# KinectIP.net
KiCad netlist of a schematic drawn in EAGLE
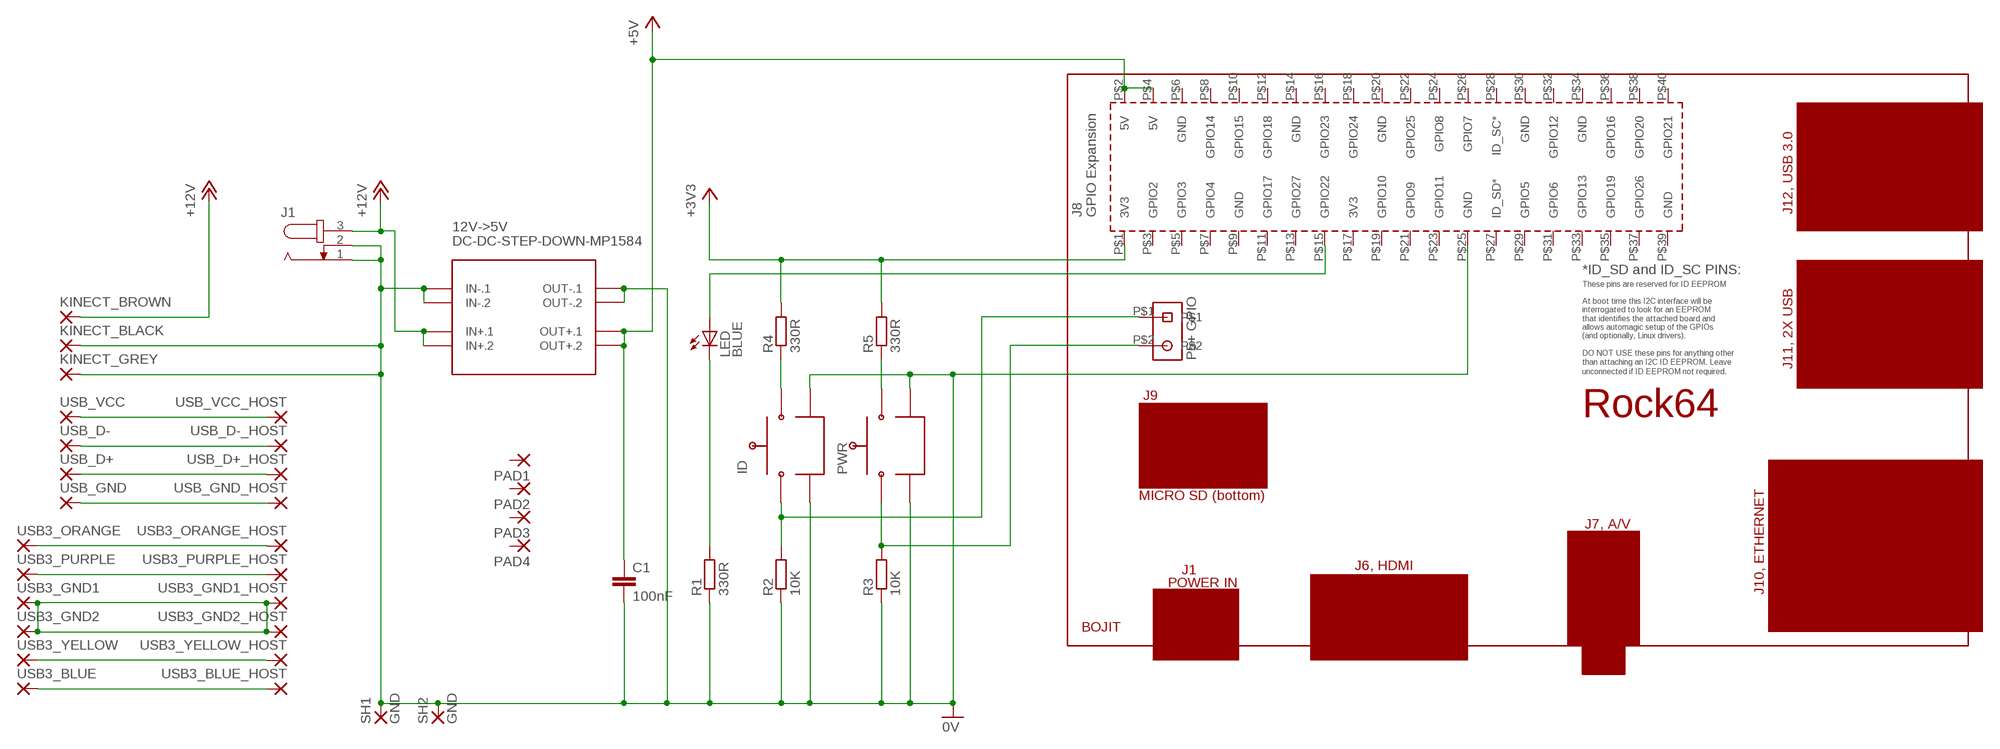
[diagram p0: schematic, sheet 1]

(export (version "E")
  (design (tool "Eeschema 10.0.6"))
  (components
    (comp (ref "12V->5V")
      (value "DC-DC-STEP-DOWN-MP1584")
      (footprint "eagle-import:DC-DC-STEP-DOWN-MP1584")
      (libsource (lib "eagle-import") (part "DC-DC-STEP-DOWN-MP1584"))
    )
    (comp (ref "C1")
      (value "100nF")
      (footprint "eagle-import:C0805K")
      (libsource (lib "eagle-import") (part "C-EUC0805K"))
    )
    (comp (ref "ID")
      (value "RIGHT-ANGLE-SWITCH")
      (footprint "eagle-import:RIGHT-ANGLE-SWITCH")
      (libsource (lib "eagle-import") (part "RIGHT-ANGLE-SWITCH"))
    )
    (comp (ref "J1")
      (value "JACK-PLUG-SLOTTED0")
      (footprint "eagle-import:SPC4077")
      (libsource (lib "eagle-import") (part "JACK-PLUG-SLOTTED0"))
    )
    (comp (ref "KINECT_BLACK")
      (value "SMD2")
      (footprint "eagle-import:SMD1,27-2,54")
      (libsource (lib "eagle-import") (part "SMD2"))
    )
    (comp (ref "KINECT_BROWN")
      (value "SMD2")
      (footprint "eagle-import:SMD1,27-2,54")
      (libsource (lib "eagle-import") (part "SMD2"))
    )
    (comp (ref "KINECT_GREY")
      (value "SMD2")
      (footprint "eagle-import:SMD1,27-2,54")
      (libsource (lib "eagle-import") (part "SMD2"))
    )
    (comp (ref "LED")
      (value "BLUE")
      (footprint "eagle-import:LED-90-DEG")
      (libsource (lib "eagle-import") (part "LED-90-DEG"))
    )
    (comp (ref "P5+")
      (value "2PIN-FEMALE-HEADER")
      (footprint "eagle-import:2PIN-FEMALE-HEADER")
      (libsource (lib "eagle-import") (part "2PIN-FEMALE-HEADER"))
    )
    (comp (ref "PAD1")
      (value "1,6/0,8")
      (footprint "eagle-import:1,6_0,8")
      (libsource (lib "eagle-import") (part "1,6/0,8"))
    )
    (comp (ref "PAD2")
      (value "1,6/0,8")
      (footprint "eagle-import:1,6_0,8")
      (libsource (lib "eagle-import") (part "1,6/0,8"))
    )
    (comp (ref "PAD3")
      (value "1,6/0,8")
      (footprint "eagle-import:1,6_0,8")
      (libsource (lib "eagle-import") (part "1,6/0,8"))
    )
    (comp (ref "PAD4")
      (value "1,6/0,8")
      (footprint "eagle-import:1,6_0,8")
      (libsource (lib "eagle-import") (part "1,6/0,8"))
    )
    (comp (ref "PCB2")
      (value "ROCK64ROCK64")
      (footprint "eagle-import:ROCK64")
      (libsource (lib "eagle-import") (part "ROCK64ROCK64"))
    )
    (comp (ref "PWR")
      (value "RIGHT-ANGLE-SWITCH")
      (footprint "eagle-import:RIGHT-ANGLE-SWITCH")
      (libsource (lib "eagle-import") (part "RIGHT-ANGLE-SWITCH"))
    )
    (comp (ref "R1")
      (value "330R")
      (footprint "eagle-import:R0805")
      (libsource (lib "eagle-import") (part "R-EU_R0805"))
    )
    (comp (ref "R2")
      (value "10K")
      (footprint "eagle-import:R0805")
      (libsource (lib "eagle-import") (part "R-EU_R0805"))
    )
    (comp (ref "R3")
      (value "10K")
      (footprint "eagle-import:R0805")
      (libsource (lib "eagle-import") (part "R-EU_R0805"))
    )
    (comp (ref "R4")
      (value "330R")
      (footprint "eagle-import:R0805")
      (libsource (lib "eagle-import") (part "R-EU_R0805"))
    )
    (comp (ref "R5")
      (value "330R")
      (footprint "eagle-import:R0805")
      (libsource (lib "eagle-import") (part "R-EU_R0805"))
    )
    (comp (ref "SH1")
      (value "GND")
      (footprint "eagle-import:SMD2,54-5,08")
      (libsource (lib "eagle-import") (part "SMD5"))
    )
    (comp (ref "SH2")
      (value "GND")
      (footprint "eagle-import:SMD2,54-5,08")
      (libsource (lib "eagle-import") (part "SMD5"))
    )
    (comp (ref "U$1")
      (value "BOJIT_COPPER")
      (footprint "eagle-import:BOJIT_LARGE_COPPER")
      (libsource (lib "eagle-import") (part "BOJIT_COPPER"))
    )
    (comp (ref "USB3_BLUE")
      (value "SMD2")
      (footprint "eagle-import:SMD1,27-2,54")
      (libsource (lib "eagle-import") (part "SMD2"))
    )
    (comp (ref "USB3_BLUE_HOST")
      (value "SMD2")
      (footprint "eagle-import:SMD1,27-2,54")
      (libsource (lib "eagle-import") (part "SMD2"))
    )
    (comp (ref "USB3_GND1")
      (value "SMD2")
      (footprint "eagle-import:SMD1,27-2,54")
      (libsource (lib "eagle-import") (part "SMD2"))
    )
    (comp (ref "USB3_GND1_HOST")
      (value "SMD2")
      (footprint "eagle-import:SMD1,27-2,54")
      (libsource (lib "eagle-import") (part "SMD2"))
    )
    (comp (ref "USB3_GND2")
      (value "SMD2")
      (footprint "eagle-import:SMD1,27-2,54")
      (libsource (lib "eagle-import") (part "SMD2"))
    )
    (comp (ref "USB3_GND2_HOST")
      (value "SMD2")
      (footprint "eagle-import:SMD1,27-2,54")
      (libsource (lib "eagle-import") (part "SMD2"))
    )
    (comp (ref "USB3_ORANGE")
      (value "SMD2")
      (footprint "eagle-import:SMD1,27-2,54")
      (libsource (lib "eagle-import") (part "SMD2"))
    )
    (comp (ref "USB3_ORANGE_HOST")
      (value "SMD2")
      (footprint "eagle-import:SMD1,27-2,54")
      (libsource (lib "eagle-import") (part "SMD2"))
    )
    (comp (ref "USB3_PURPLE")
      (value "SMD2")
      (footprint "eagle-import:SMD1,27-2,54")
      (libsource (lib "eagle-import") (part "SMD2"))
    )
    (comp (ref "USB3_PURPLE_HOST")
      (value "SMD2")
      (footprint "eagle-import:SMD1,27-2,54")
      (libsource (lib "eagle-import") (part "SMD2"))
    )
    (comp (ref "USB3_YELLOW")
      (value "SMD2")
      (footprint "eagle-import:SMD1,27-2,54")
      (libsource (lib "eagle-import") (part "SMD2"))
    )
    (comp (ref "USB3_YELLOW_HOST")
      (value "SMD2")
      (footprint "eagle-import:SMD1,27-2,54")
      (libsource (lib "eagle-import") (part "SMD2"))
    )
    (comp (ref "USB_D+")
      (value "SMD2")
      (footprint "eagle-import:SMD1,27-2,54")
      (libsource (lib "eagle-import") (part "SMD2"))
    )
    (comp (ref "USB_D+_HOST")
      (value "SMD2")
      (footprint "eagle-import:SMD1,27-2,54")
      (libsource (lib "eagle-import") (part "SMD2"))
    )
    (comp (ref "USB_D-")
      (value "SMD2")
      (footprint "eagle-import:SMD1,27-2,54")
      (libsource (lib "eagle-import") (part "SMD2"))
    )
    (comp (ref "USB_D-_HOST")
      (value "SMD2")
      (footprint "eagle-import:SMD1,27-2,54")
      (libsource (lib "eagle-import") (part "SMD2"))
    )
    (comp (ref "USB_GND")
      (value "SMD2")
      (footprint "eagle-import:SMD1,27-2,54")
      (libsource (lib "eagle-import") (part "SMD2"))
    )
    (comp (ref "USB_GND_HOST")
      (value "SMD2")
      (footprint "eagle-import:SMD1,27-2,54")
      (libsource (lib "eagle-import") (part "SMD2"))
    )
    (comp (ref "USB_VCC")
      (value "SMD2")
      (footprint "eagle-import:SMD1,27-2,54")
      (libsource (lib "eagle-import") (part "SMD2"))
    )
    (comp (ref "USB_VCC_HOST")
      (value "SMD2")
      (footprint "eagle-import:SMD1,27-2,54")
      (libsource (lib "eagle-import") (part "SMD2"))
    )
  )
  (nets
    (net (code "1") (name "+3V3") (class "Default")
      (node (ref "PCB2") (pin "P$1") (pinfunction "3V3_P$1") (pintype "bidirectional"))
      (node (ref "R4") (pin "2") (pinfunction "2_2") (pintype "passive"))
      (node (ref "R5") (pin "2") (pinfunction "2_2") (pintype "passive"))
    )
    (net (code "2") (name "+5V") (class "Default")
      (node (ref "12V->5V") (pin "OUT+.1") (pinfunction "OUT+.1_OUT+.1") (pintype "bidirectional"))
      (node (ref "12V->5V") (pin "OUT+.2") (pinfunction "OUT+.2_OUT+.2") (pintype "bidirectional"))
      (node (ref "C1") (pin "1") (pinfunction "1_1") (pintype "passive"))
      (node (ref "PCB2") (pin "P$2") (pinfunction "5V_P$2") (pintype "bidirectional"))
      (node (ref "PCB2") (pin "P$4") (pinfunction "5V_P$4") (pintype "bidirectional"))
    )
    (net (code "3") (name "+12V") (class "Default")
      (node (ref "12V->5V") (pin "IN+.1") (pinfunction "IN+.1_IN+.1") (pintype "bidirectional"))
      (node (ref "12V->5V") (pin "IN+.2") (pinfunction "IN+.2_IN+.2") (pintype "bidirectional"))
      (node (ref "J1") (pin "3") (pinfunction "3_3") (pintype "passive"))
      (node (ref "KINECT_BROWN") (pin "1") (pinfunction "P_1") (pintype "passive"))
    )
    (net (code "4") (name "0V") (class "Default")
      (node (ref "12V->5V") (pin "IN-.1") (pinfunction "IN-.1_IN-.1") (pintype "bidirectional"))
      (node (ref "12V->5V") (pin "IN-.2") (pinfunction "IN-.2_IN-.2") (pintype "bidirectional"))
      (node (ref "12V->5V") (pin "OUT-.1") (pinfunction "OUT-.1_OUT-.1") (pintype "bidirectional"))
      (node (ref "12V->5V") (pin "OUT-.2") (pinfunction "OUT-.2_OUT-.2") (pintype "bidirectional"))
      (node (ref "C1") (pin "2") (pinfunction "2_2") (pintype "passive"))
      (node (ref "ID") (pin "MNT$1") (pinfunction "MNT$1_MNT$1") (pintype "passive"))
      (node (ref "ID") (pin "MNT$2") (pinfunction "MNT$2_MNT$2") (pintype "passive"))
      (node (ref "J1") (pin "1") (pinfunction "1_1") (pintype "passive"))
      (node (ref "J1") (pin "2") (pinfunction "2_2") (pintype "passive"))
      (node (ref "KINECT_BLACK") (pin "1") (pinfunction "P_1") (pintype "passive"))
      (node (ref "KINECT_GREY") (pin "1") (pinfunction "P_1") (pintype "passive"))
      (node (ref "PCB2") (pin "P$25") (pinfunction "GND_P$25") (pintype "bidirectional"))
      (node (ref "PWR") (pin "MNT$1") (pinfunction "MNT$1_MNT$1") (pintype "passive"))
      (node (ref "PWR") (pin "MNT$2") (pinfunction "MNT$2_MNT$2") (pintype "passive"))
      (node (ref "R1") (pin "1") (pinfunction "1_1") (pintype "passive"))
      (node (ref "R2") (pin "1") (pinfunction "1_1") (pintype "passive"))
      (node (ref "R3") (pin "1") (pinfunction "1_1") (pintype "passive"))
      (node (ref "SH1") (pin "1") (pinfunction "P_1") (pintype "passive"))
      (node (ref "SH2") (pin "1") (pinfunction "P_1") (pintype "passive"))
    )
    (net (code "5") (name "Net-(ID-PadSW$1)") (class "Default")
      (node (ref "ID") (pin "SW$1") (pinfunction "SW$1_SW$1") (pintype "bidirectional"))
      (node (ref "P5+") (pin "P$1") (pinfunction "P$1_P$1") (pintype "bidirectional"))
      (node (ref "R2") (pin "2") (pinfunction "2_2") (pintype "passive"))
    )
    (net (code "6") (name "Net-(ID-PadSW$2)") (class "Default")
      (node (ref "ID") (pin "SW$2") (pinfunction "SW$2_SW$2") (pintype "bidirectional"))
      (node (ref "R4") (pin "1") (pinfunction "1_1") (pintype "passive"))
    )
    (net (code "7") (name "Net-(LED-C)") (class "Default")
      (node (ref "LED") (pin "K") (pinfunction "C_K") (pintype "passive"))
      (node (ref "R1") (pin "2") (pinfunction "2_2") (pintype "passive"))
    )
    (net (code "8") (name "Net-(P5+-PadP$2)") (class "Default")
      (node (ref "P5+") (pin "P$2") (pinfunction "P$2_P$2") (pintype "bidirectional"))
      (node (ref "PWR") (pin "SW$1") (pinfunction "SW$1_SW$1") (pintype "bidirectional"))
      (node (ref "R3") (pin "2") (pinfunction "2_2") (pintype "passive"))
    )
    (net (code "9") (name "Net-(PCB2-GPIO22)") (class "Default")
      (node (ref "LED") (pin "A") (pinfunction "A_A") (pintype "passive"))
      (node (ref "PCB2") (pin "P$15") (pinfunction "GPIO22_P$15") (pintype "bidirectional"))
    )
    (net (code "10") (name "Net-(PWR-PadSW$2)") (class "Default")
      (node (ref "PWR") (pin "SW$2") (pinfunction "SW$2_SW$2") (pintype "bidirectional"))
      (node (ref "R5") (pin "1") (pinfunction "1_1") (pintype "passive"))
    )
    (net (code "11") (name "Net-(USB3_BLUE-P)") (class "Default")
      (node (ref "USB3_BLUE") (pin "1") (pinfunction "P_1") (pintype "passive"))
      (node (ref "USB3_BLUE_HOST") (pin "1") (pinfunction "P_1") (pintype "passive"))
    )
    (net (code "12") (name "Net-(USB3_GND1-P)") (class "Default")
      (node (ref "USB3_GND1") (pin "1") (pinfunction "P_1") (pintype "passive"))
      (node (ref "USB3_GND1_HOST") (pin "1") (pinfunction "P_1") (pintype "passive"))
      (node (ref "USB3_GND2") (pin "1") (pinfunction "P_1") (pintype "passive"))
      (node (ref "USB3_GND2_HOST") (pin "1") (pinfunction "P_1") (pintype "passive"))
    )
    (net (code "13") (name "Net-(USB3_ORANGE-P)") (class "Default")
      (node (ref "USB3_ORANGE") (pin "1") (pinfunction "P_1") (pintype "passive"))
      (node (ref "USB3_ORANGE_HOST") (pin "1") (pinfunction "P_1") (pintype "passive"))
    )
    (net (code "14") (name "Net-(USB3_PURPLE-P)") (class "Default")
      (node (ref "USB3_PURPLE") (pin "1") (pinfunction "P_1") (pintype "passive"))
      (node (ref "USB3_PURPLE_HOST") (pin "1") (pinfunction "P_1") (pintype "passive"))
    )
    (net (code "15") (name "Net-(USB3_YELLOW-P)") (class "Default")
      (node (ref "USB3_YELLOW") (pin "1") (pinfunction "P_1") (pintype "passive"))
      (node (ref "USB3_YELLOW_HOST") (pin "1") (pinfunction "P_1") (pintype "passive"))
    )
    (net (code "16") (name "Net-(USB_D+-P)") (class "Default")
      (node (ref "USB_D+") (pin "1") (pinfunction "P_1") (pintype "passive"))
      (node (ref "USB_D+_HOST") (pin "1") (pinfunction "P_1") (pintype "passive"))
    )
    (net (code "17") (name "Net-(USB_D--P)") (class "Default")
      (node (ref "USB_D-") (pin "1") (pinfunction "P_1") (pintype "passive"))
      (node (ref "USB_D-_HOST") (pin "1") (pinfunction "P_1") (pintype "passive"))
    )
    (net (code "18") (name "Net-(USB_GND-P)") (class "Default")
      (node (ref "USB_GND") (pin "1") (pinfunction "P_1") (pintype "passive"))
      (node (ref "USB_GND_HOST") (pin "1") (pinfunction "P_1") (pintype "passive"))
    )
    (net (code "19") (name "Net-(USB_VCC-P)") (class "Default")
      (node (ref "USB_VCC") (pin "1") (pinfunction "P_1") (pintype "passive"))
      (node (ref "USB_VCC_HOST") (pin "1") (pinfunction "P_1") (pintype "passive"))
    )
    (net (code "20") (name "unconnected-(PAD1-P-Pad1)") (class "Default")
      (node (ref "PAD1") (pin "1") (pinfunction "P_1") (pintype "passive"))
    )
    (net (code "21") (name "unconnected-(PAD2-P-Pad1)") (class "Default")
      (node (ref "PAD2") (pin "1") (pinfunction "P_1") (pintype "passive"))
    )
    (net (code "22") (name "unconnected-(PAD3-P-Pad1)") (class "Default")
      (node (ref "PAD3") (pin "1") (pinfunction "P_1") (pintype "passive"))
    )
    (net (code "23") (name "unconnected-(PAD4-P-Pad1)") (class "Default")
      (node (ref "PAD4") (pin "1") (pinfunction "P_1") (pintype "passive"))
    )
    (net (code "24") (name "unconnected-(PCB2-3V3-PadP$17)") (class "Default")
      (node (ref "PCB2") (pin "P$17") (pinfunction "3V3_P$17") (pintype "bidirectional"))
    )
    (net (code "25") (name "unconnected-(PCB2-GND-PadP$6)") (class "Default")
      (node (ref "PCB2") (pin "P$6") (pinfunction "GND_P$6") (pintype "bidirectional"))
    )
    (net (code "26") (name "unconnected-(PCB2-GND-PadP$9)") (class "Default")
      (node (ref "PCB2") (pin "P$9") (pinfunction "GND_P$9") (pintype "bidirectional"))
    )
    (net (code "27") (name "unconnected-(PCB2-GND-PadP$14)") (class "Default")
      (node (ref "PCB2") (pin "P$14") (pinfunction "GND_P$14") (pintype "bidirectional"))
    )
    (net (code "28") (name "unconnected-(PCB2-GND-PadP$20)") (class "Default")
      (node (ref "PCB2") (pin "P$20") (pinfunction "GND_P$20") (pintype "bidirectional"))
    )
    (net (code "29") (name "unconnected-(PCB2-GND-PadP$30)") (class "Default")
      (node (ref "PCB2") (pin "P$30") (pinfunction "GND_P$30") (pintype "bidirectional"))
    )
    (net (code "30") (name "unconnected-(PCB2-GND-PadP$34)") (class "Default")
      (node (ref "PCB2") (pin "P$34") (pinfunction "GND_P$34") (pintype "bidirectional"))
    )
    (net (code "31") (name "unconnected-(PCB2-GND-PadP$39)") (class "Default")
      (node (ref "PCB2") (pin "P$39") (pinfunction "GND_P$39") (pintype "bidirectional"))
    )
    (net (code "32") (name "unconnected-(PCB2-GPIO2-PadP$3)") (class "Default")
      (node (ref "PCB2") (pin "P$3") (pinfunction "GPIO2_P$3") (pintype "bidirectional"))
    )
    (net (code "33") (name "unconnected-(PCB2-GPIO3-PadP$5)") (class "Default")
      (node (ref "PCB2") (pin "P$5") (pinfunction "GPIO3_P$5") (pintype "bidirectional"))
    )
    (net (code "34") (name "unconnected-(PCB2-GPIO4-PadP$7)") (class "Default")
      (node (ref "PCB2") (pin "P$7") (pinfunction "GPIO4_P$7") (pintype "bidirectional"))
    )
    (net (code "35") (name "unconnected-(PCB2-GPIO5-PadP$29)") (class "Default")
      (node (ref "PCB2") (pin "P$29") (pinfunction "GPIO5_P$29") (pintype "bidirectional"))
    )
    (net (code "36") (name "unconnected-(PCB2-GPIO6-PadP$31)") (class "Default")
      (node (ref "PCB2") (pin "P$31") (pinfunction "GPIO6_P$31") (pintype "bidirectional"))
    )
    (net (code "37") (name "unconnected-(PCB2-GPIO7-PadP$26)") (class "Default")
      (node (ref "PCB2") (pin "P$26") (pinfunction "GPIO7_P$26") (pintype "bidirectional"))
    )
    (net (code "38") (name "unconnected-(PCB2-GPIO8-PadP$24)") (class "Default")
      (node (ref "PCB2") (pin "P$24") (pinfunction "GPIO8_P$24") (pintype "bidirectional"))
    )
    (net (code "39") (name "unconnected-(PCB2-GPIO9-PadP$21)") (class "Default")
      (node (ref "PCB2") (pin "P$21") (pinfunction "GPIO9_P$21") (pintype "bidirectional"))
    )
    (net (code "40") (name "unconnected-(PCB2-GPIO10-PadP$19)") (class "Default")
      (node (ref "PCB2") (pin "P$19") (pinfunction "GPIO10_P$19") (pintype "bidirectional"))
    )
    (net (code "41") (name "unconnected-(PCB2-GPIO11-PadP$23)") (class "Default")
      (node (ref "PCB2") (pin "P$23") (pinfunction "GPIO11_P$23") (pintype "bidirectional"))
    )
    (net (code "42") (name "unconnected-(PCB2-GPIO12-PadP$32)") (class "Default")
      (node (ref "PCB2") (pin "P$32") (pinfunction "GPIO12_P$32") (pintype "bidirectional"))
    )
    (net (code "43") (name "unconnected-(PCB2-GPIO13-PadP$33)") (class "Default")
      (node (ref "PCB2") (pin "P$33") (pinfunction "GPIO13_P$33") (pintype "bidirectional"))
    )
    (net (code "44") (name "unconnected-(PCB2-GPIO14-PadP$8)") (class "Default")
      (node (ref "PCB2") (pin "P$8") (pinfunction "GPIO14_P$8") (pintype "bidirectional"))
    )
    (net (code "45") (name "unconnected-(PCB2-GPIO15-PadP$10)") (class "Default")
      (node (ref "PCB2") (pin "P$10") (pinfunction "GPIO15_P$10") (pintype "bidirectional"))
    )
    (net (code "46") (name "unconnected-(PCB2-GPIO16-PadP$36)") (class "Default")
      (node (ref "PCB2") (pin "P$36") (pinfunction "GPIO16_P$36") (pintype "bidirectional"))
    )
    (net (code "47") (name "unconnected-(PCB2-GPIO17-PadP$11)") (class "Default")
      (node (ref "PCB2") (pin "P$11") (pinfunction "GPIO17_P$11") (pintype "bidirectional"))
    )
    (net (code "48") (name "unconnected-(PCB2-GPIO18-PadP$12)") (class "Default")
      (node (ref "PCB2") (pin "P$12") (pinfunction "GPIO18_P$12") (pintype "bidirectional"))
    )
    (net (code "49") (name "unconnected-(PCB2-GPIO19-PadP$35)") (class "Default")
      (node (ref "PCB2") (pin "P$35") (pinfunction "GPIO19_P$35") (pintype "bidirectional"))
    )
    (net (code "50") (name "unconnected-(PCB2-GPIO20-PadP$38)") (class "Default")
      (node (ref "PCB2") (pin "P$38") (pinfunction "GPIO20_P$38") (pintype "bidirectional"))
    )
    (net (code "51") (name "unconnected-(PCB2-GPIO21-PadP$40)") (class "Default")
      (node (ref "PCB2") (pin "P$40") (pinfunction "GPIO21_P$40") (pintype "bidirectional"))
    )
    (net (code "52") (name "unconnected-(PCB2-GPIO23-PadP$16)") (class "Default")
      (node (ref "PCB2") (pin "P$16") (pinfunction "GPIO23_P$16") (pintype "bidirectional"))
    )
    (net (code "53") (name "unconnected-(PCB2-GPIO24-PadP$18)") (class "Default")
      (node (ref "PCB2") (pin "P$18") (pinfunction "GPIO24_P$18") (pintype "bidirectional"))
    )
    (net (code "54") (name "unconnected-(PCB2-GPIO25-PadP$22)") (class "Default")
      (node (ref "PCB2") (pin "P$22") (pinfunction "GPIO25_P$22") (pintype "bidirectional"))
    )
    (net (code "55") (name "unconnected-(PCB2-GPIO26-PadP$37)") (class "Default")
      (node (ref "PCB2") (pin "P$37") (pinfunction "GPIO26_P$37") (pintype "bidirectional"))
    )
    (net (code "56") (name "unconnected-(PCB2-GPIO27-PadP$13)") (class "Default")
      (node (ref "PCB2") (pin "P$13") (pinfunction "GPIO27_P$13") (pintype "bidirectional"))
    )
    (net (code "57") (name "unconnected-(PCB2-ID_SC*-PadP$28)") (class "Default")
      (node (ref "PCB2") (pin "P$28") (pinfunction "ID_SC*_P$28") (pintype "bidirectional"))
    )
    (net (code "58") (name "unconnected-(PCB2-ID_SD*-PadP$27)") (class "Default")
      (node (ref "PCB2") (pin "P$27") (pinfunction "ID_SD*_P$27") (pintype "bidirectional"))
    )
  )
)
